# OSD_y_Memoria.net
KiCad netlist of a schematic drawn in Altium Designer
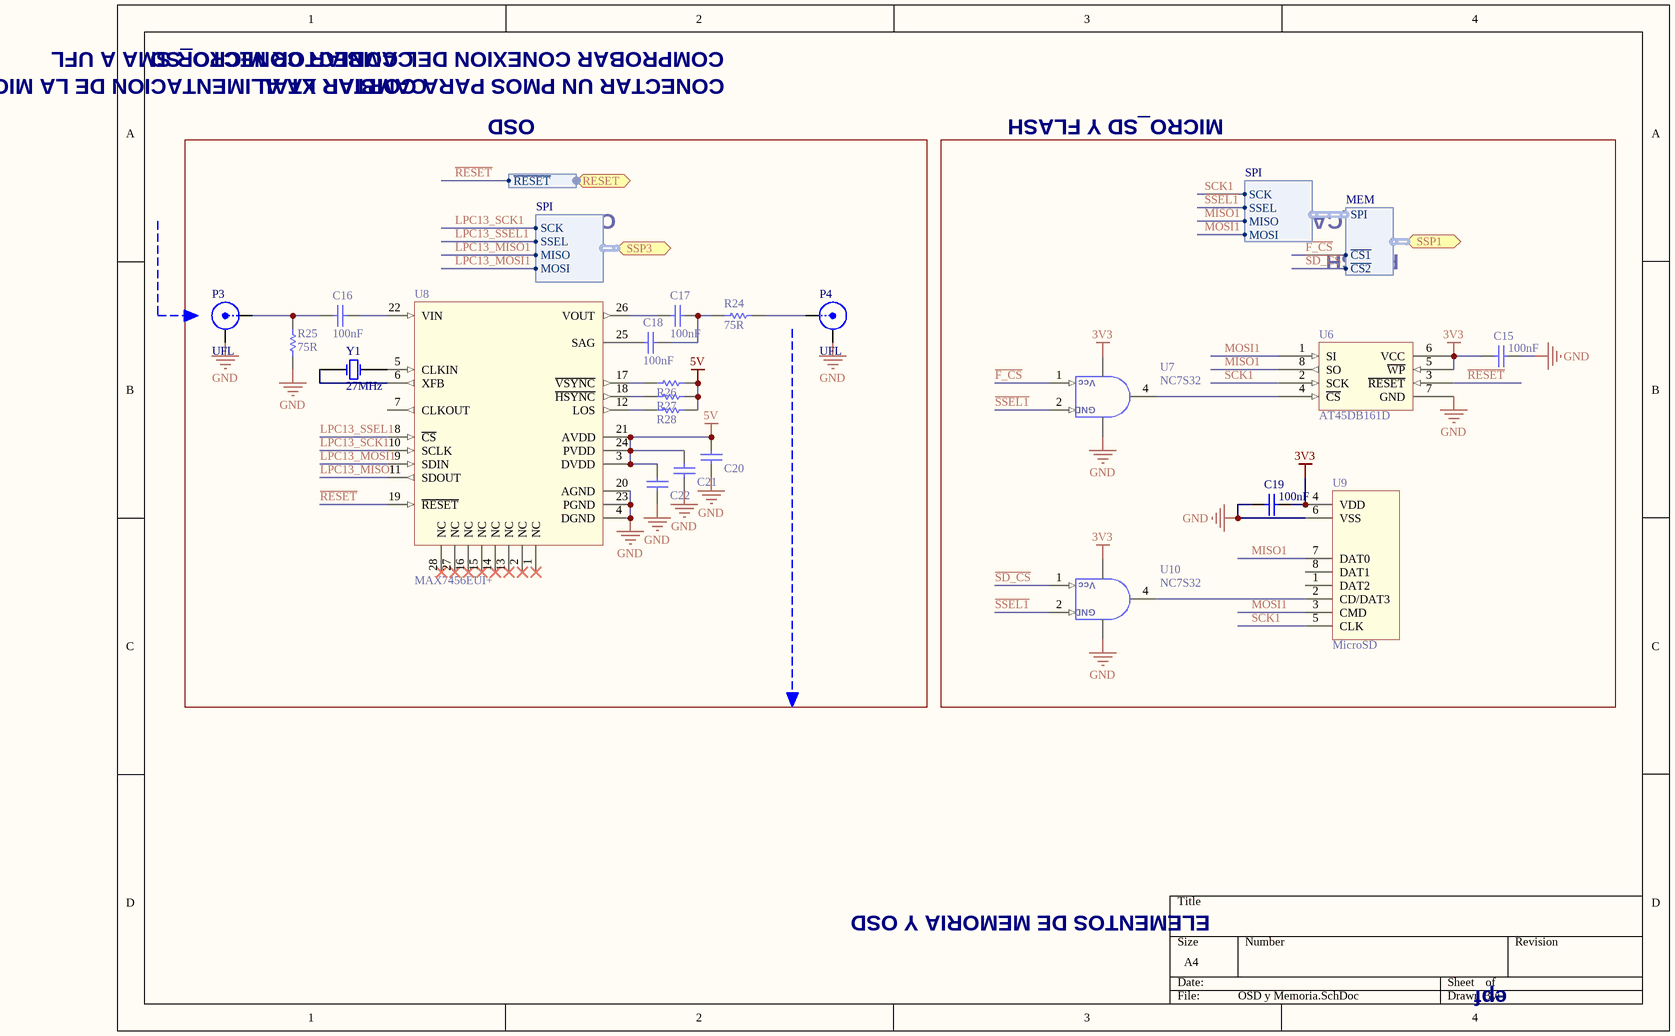
[diagram p0: OSD y Memoria.SchDoc]

(export (version "E")
  (design (tool "Eeschema 10.0.6"))
  (components
    (comp (ref "C15")
      (value "100nF")
      (footprint "CAP0402")
      (fields (field (name "Comment") "Capacitor"))
      (libsource (lib "epf") (part "Cap"))
    )
    (comp (ref "C16")
      (value "100nF")
      (footprint "CAP0402")
      (fields (field (name "Comment") "Capacitor"))
      (libsource (lib "epf") (part "Cap"))
    )
    (comp (ref "C17")
      (value "100nF")
      (footprint "CAP0402")
      (fields (field (name "Comment") "Capacitor"))
      (libsource (lib "epf") (part "Cap"))
    )
    (comp (ref "C18")
      (value "100nF")
      (footprint "CAP0402")
      (fields (field (name "Comment") "Capacitor"))
      (libsource (lib "epf") (part "Cap"))
    )
    (comp (ref "C19")
      (value "100nF")
      (footprint "CAP0402")
      (fields (field (name "Comment") "Capacitor"))
      (libsource (lib "epf") (part "Cap"))
    )
    (comp (ref "C20") (value "Capacitor") (footprint "CAP0402") (libsource (lib "epf") (part "Cap")))
    (comp (ref "C21") (value "Capacitor") (footprint "CAP0402") (libsource (lib "epf") (part "Cap")))
    (comp (ref "C22") (value "Capacitor") (footprint "CAP0402") (libsource (lib "epf") (part "Cap")))
    (comp (ref "P3") (value "UFL") (footprint "UFL") (libsource (lib "epf") (part "UFL")))
    (comp (ref "P4") (value "UFL") (footprint "UFL") (libsource (lib "epf") (part "UFL")))
    (comp (ref "R24")
      (value "75R")
      (footprint "RES0402")
      (fields (field (name "Comment") "Resistor"))
      (libsource (lib "epf") (part "Res"))
    )
    (comp (ref "R25")
      (value "75R")
      (footprint "RES0402")
      (fields (field (name "Comment") "Resistor"))
      (libsource (lib "epf") (part "Res"))
    )
    (comp (ref "R26") (value "Resistor") (footprint "RES0402") (libsource (lib "epf") (part "Res")))
    (comp (ref "R27") (value "Resistor") (footprint "RES0402") (libsource (lib "epf") (part "Res")))
    (comp (ref "R28") (value "Resistor") (footprint "RES0402") (libsource (lib "epf") (part "Res")))
    (comp (ref "U6")
      (value "AT45DB161D")
      (footprint "SOIC127P600-8CN")
      (description "Data Flash")
      (libsource (lib "epf") (part "AT45DB161D"))
    )
    (comp (ref "U7")
      (value "NC7S32")
      (footprint "SOT23-5BN")
      (description "OR GATE")
      (libsource (lib "epf") (part "NC7S32"))
    )
    (comp (ref "U8")
      (value "MAX7456EUI+")
      (footprint "TSOP65P640-28AN")
      (description "OSD Display")
      (libsource (lib "epf") (part "MAX7456EUI+"))
    )
    (comp (ref "U9") (value "MicroSD") (footprint "101-00303") (libsource (lib "epf") (part "MicroSD")))
    (comp (ref "U10")
      (value "NC7S32")
      (footprint "SOT23-5BN")
      (description "OR GATE")
      (libsource (lib "epf") (part "NC7S32"))
    )
    (comp (ref "Y1")
      (value "27MHz")
      (footprint "HC/49US")
      (description "Crystal Oscillator")
      (fields (field (name "PUBLISHER") "Altium Limited"))
      (libsource (lib "epf") (part "XTAL"))
    )
  )
  (nets
    (net (code "3") (name "/F_CS") (class "Default")
      (node (ref "U7") (pin "1") (pinfunction "A_1") (pintype "input"))
    )
    (net (code "4") (name "/LPC13_MISO1") (class "Default")
      (node (ref "U8") (pin "11") (pinfunction "SDOUT_11") (pintype "output"))
    )
    (net (code "5") (name "/LPC13_MOSI1") (class "Default")
      (node (ref "U8") (pin "9") (pinfunction "SDIN_9") (pintype "input"))
    )
    (net (code "6") (name "/LPC13_SCK1") (class "Default")
      (node (ref "U8") (pin "10") (pinfunction "SCLK_10") (pintype "input"))
    )
    (net (code "7") (name "/LPC13_SSEL1") (class "Default")
      (node (ref "U8") (pin "8") (pinfunction "CS_8") (pintype "input"))
    )
    (net (code "8") (name "/MISO1") (class "Default")
      (node (ref "U6") (pin "8") (pinfunction "SO_8") (pintype "output"))
      (node (ref "U9") (pin "7") (pinfunction "DAT0_7") (pintype "passive"))
    )
    (net (code "9") (name "/MOSI1") (class "Default")
      (node (ref "U6") (pin "1") (pinfunction "SI_1") (pintype "input"))
      (node (ref "U9") (pin "3") (pinfunction "CMD_3") (pintype "passive"))
    )
    (net (code "10") (name "/RESET") (class "Default")
      (node (ref "U6") (pin "3") (pinfunction "RESET_3") (pintype "input"))
      (node (ref "U8") (pin "19") (pinfunction "RESET_19") (pintype "input"))
    )
    (net (code "11") (name "/SCK1") (class "Default")
      (node (ref "U6") (pin "2") (pinfunction "SCK_2") (pintype "input"))
      (node (ref "U9") (pin "5") (pinfunction "CLK_5") (pintype "passive"))
    )
    (net (code "12") (name "/SD_CS") (class "Default")
      (node (ref "U10") (pin "1") (pinfunction "A_1") (pintype "input"))
    )
    (net (code "13") (name "/SSEL1") (class "Default")
      (node (ref "U10") (pin "2") (pinfunction "B_2") (pintype "input"))
      (node (ref "U7") (pin "2") (pinfunction "B_2") (pintype "input"))
    )
    (net (code "17") (name "3V3") (class "Default")
      (node (ref "C15") (pin "1") (pinfunction "1_1") (pintype "passive"))
      (node (ref "C19") (pin "2") (pinfunction "2_2") (pintype "passive"))
      (node (ref "U10") (pin "5") (pinfunction "VCC_5") (pintype "power_in"))
      (node (ref "U6") (pin "5") (pinfunction "WP_5") (pintype "input"))
      (node (ref "U6") (pin "6") (pinfunction "VCC_6") (pintype "power_in"))
      (node (ref "U7") (pin "5") (pinfunction "VCC_5") (pintype "power_in"))
      (node (ref "U9") (pin "4") (pinfunction "VDD_4") (pintype "passive"))
    )
    (net (code "18") (name "5V") (class "Default")
      (node (ref "C20") (pin "2") (pinfunction "2_2") (pintype "passive"))
      (node (ref "C21") (pin "2") (pinfunction "2_2") (pintype "passive"))
      (node (ref "C22") (pin "2") (pinfunction "2_2") (pintype "passive"))
      (node (ref "R26") (pin "2") (pinfunction "2_2") (pintype "passive"))
      (node (ref "R27") (pin "2") (pinfunction "2_2") (pintype "passive"))
      (node (ref "R28") (pin "2") (pinfunction "2_2") (pintype "passive"))
      (node (ref "U8") (pin "21") (pinfunction "AVDD_21") (pintype "power_in"))
      (node (ref "U8") (pin "24") (pinfunction "PVDD_24") (pintype "power_in"))
      (node (ref "U8") (pin "3") (pinfunction "DVDD_3") (pintype "power_in"))
    )
    (net (code "19") (name "GND") (class "Default")
      (node (ref "C15") (pin "2") (pinfunction "2_2") (pintype "passive"))
      (node (ref "C19") (pin "1") (pinfunction "1_1") (pintype "passive"))
      (node (ref "C20") (pin "1") (pinfunction "1_1") (pintype "passive"))
      (node (ref "C21") (pin "1") (pinfunction "1_1") (pintype "passive"))
      (node (ref "C22") (pin "1") (pinfunction "1_1") (pintype "passive"))
      (node (ref "P3") (pin "2") (pinfunction "Y_2") (pintype "passive"))
      (node (ref "P4") (pin "2") (pinfunction "Y_2") (pintype "passive"))
      (node (ref "R25") (pin "1") (pinfunction "1_1") (pintype "passive"))
      (node (ref "U10") (pin "3") (pinfunction "GND_3") (pintype "power_in"))
      (node (ref "U6") (pin "7") (pinfunction "GND_7") (pintype "power_in"))
      (node (ref "U7") (pin "3") (pinfunction "GND_3") (pintype "power_in"))
      (node (ref "U8") (pin "20") (pinfunction "AGND_20") (pintype "power_in"))
      (node (ref "U8") (pin "23") (pinfunction "PGND_23") (pintype "power_in"))
      (node (ref "U8") (pin "4") (pinfunction "DGND_4") (pintype "power_in"))
      (node (ref "U9") (pin "6") (pinfunction "VSS_6") (pintype "passive"))
    )
    (net (code "20") (name "Net-(C17-Pad1)") (class "Default")
      (node (ref "C17") (pin "1") (pinfunction "1_1") (pintype "passive"))
      (node (ref "C18") (pin "1") (pinfunction "1_1") (pintype "passive"))
      (node (ref "R24") (pin "1") (pinfunction "1_1") (pintype "passive"))
    )
    (net (code "21") (name "Net-(P3-X)") (class "Default")
      (node (ref "C16") (pin "2") (pinfunction "2_2") (pintype "passive"))
      (node (ref "P3") (pin "1") (pinfunction "X_1") (pintype "passive"))
      (node (ref "R25") (pin "2") (pinfunction "2_2") (pintype "passive"))
    )
    (net (code "22") (name "Net-(P4-X)") (class "Default")
      (node (ref "P4") (pin "1") (pinfunction "X_1") (pintype "passive"))
      (node (ref "R24") (pin "2") (pinfunction "2_2") (pintype "passive"))
    )
    (net (code "23") (name "Net-(U6-CS)") (class "Default")
      (node (ref "U6") (pin "4") (pinfunction "CS_4") (pintype "input"))
      (node (ref "U7") (pin "4") (pinfunction "Y_4") (pintype "open_collector"))
    )
    (net (code "24") (name "Net-(U8-CLKIN)") (class "Default")
      (node (ref "U8") (pin "5") (pinfunction "CLKIN_5") (pintype "input"))
      (node (ref "Y1") (pin "2") (pinfunction "OSC2_2") (pintype "passive"))
    )
    (net (code "25") (name "Net-(U8-HSYNC)") (class "Default")
      (node (ref "R27") (pin "1") (pinfunction "1_1") (pintype "passive"))
      (node (ref "U8") (pin "18") (pinfunction "HSYNC_18") (pintype "output"))
    )
    (net (code "26") (name "Net-(U8-LOS)") (class "Default")
      (node (ref "R28") (pin "1") (pinfunction "1_1") (pintype "passive"))
      (node (ref "U8") (pin "12") (pinfunction "LOS_12") (pintype "output"))
    )
    (net (code "27") (name "Net-(U8-SAG)") (class "Default")
      (node (ref "C18") (pin "2") (pinfunction "2_2") (pintype "passive"))
      (node (ref "U8") (pin "25") (pinfunction "SAG_25") (pintype "passive"))
    )
    (net (code "28") (name "Net-(U8-VIN)") (class "Default")
      (node (ref "C16") (pin "1") (pinfunction "1_1") (pintype "passive"))
      (node (ref "U8") (pin "22") (pinfunction "VIN_22") (pintype "input"))
    )
    (net (code "29") (name "Net-(U8-VOUT)") (class "Default")
      (node (ref "C17") (pin "2") (pinfunction "2_2") (pintype "passive"))
      (node (ref "U8") (pin "26") (pinfunction "VOUT_26") (pintype "output"))
    )
    (net (code "30") (name "Net-(U8-VSYNC)") (class "Default")
      (node (ref "R26") (pin "1") (pinfunction "1_1") (pintype "passive"))
      (node (ref "U8") (pin "17") (pinfunction "VSYNC_17") (pintype "output"))
    )
    (net (code "31") (name "Net-(U8-XFB)") (class "Default")
      (node (ref "U8") (pin "6") (pinfunction "XFB_6") (pintype "output"))
      (node (ref "Y1") (pin "1") (pinfunction "OSC1_1") (pintype "passive"))
    )
    (net (code "32") (name "Net-(U10-Y)") (class "Default")
      (node (ref "U10") (pin "4") (pinfunction "Y_4") (pintype "open_collector"))
      (node (ref "U9") (pin "2") (pinfunction "CD/DAT3_2") (pintype "passive"))
    )
    (net (code "33") (name "unconnected-(U8-CLKOUT-Pad7)") (class "Default")
      (node (ref "U8") (pin "7") (pinfunction "CLKOUT_7") (pintype "output"))
    )
    (net (code "34") (name "unconnected-(U8-NC-Pad1)") (class "Default")
      (node (ref "U8") (pin "1") (pinfunction "NC_1") (pintype "passive+no_connect"))
    )
    (net (code "35") (name "unconnected-(U8-NC-Pad2)") (class "Default")
      (node (ref "U8") (pin "2") (pinfunction "NC_2") (pintype "passive+no_connect"))
    )
    (net (code "36") (name "unconnected-(U8-NC-Pad13)") (class "Default")
      (node (ref "U8") (pin "13") (pinfunction "NC_13") (pintype "passive+no_connect"))
    )
    (net (code "37") (name "unconnected-(U8-NC-Pad14)") (class "Default")
      (node (ref "U8") (pin "14") (pinfunction "NC_14") (pintype "passive+no_connect"))
    )
    (net (code "38") (name "unconnected-(U8-NC-Pad15)") (class "Default")
      (node (ref "U8") (pin "15") (pinfunction "NC_15") (pintype "passive+no_connect"))
    )
    (net (code "39") (name "unconnected-(U8-NC-Pad16)") (class "Default")
      (node (ref "U8") (pin "16") (pinfunction "NC_16") (pintype "passive+no_connect"))
    )
    (net (code "40") (name "unconnected-(U8-NC-Pad27)") (class "Default")
      (node (ref "U8") (pin "27") (pinfunction "NC_27") (pintype "passive+no_connect"))
    )
    (net (code "41") (name "unconnected-(U8-NC-Pad28)") (class "Default")
      (node (ref "U8") (pin "28") (pinfunction "NC_28") (pintype "passive+no_connect"))
    )
    (net (code "42") (name "unconnected-(U9-DAT1-Pad8)") (class "Default")
      (node (ref "U9") (pin "8") (pinfunction "DAT1_8") (pintype "passive"))
    )
    (net (code "43") (name "unconnected-(U9-DAT2-Pad1)") (class "Default")
      (node (ref "U9") (pin "1") (pinfunction "DAT2_1") (pintype "passive"))
    )
  )
)
